# ice_header_adapter_pcb.net
KiCad netlist of a schematic drawn in EAGLE
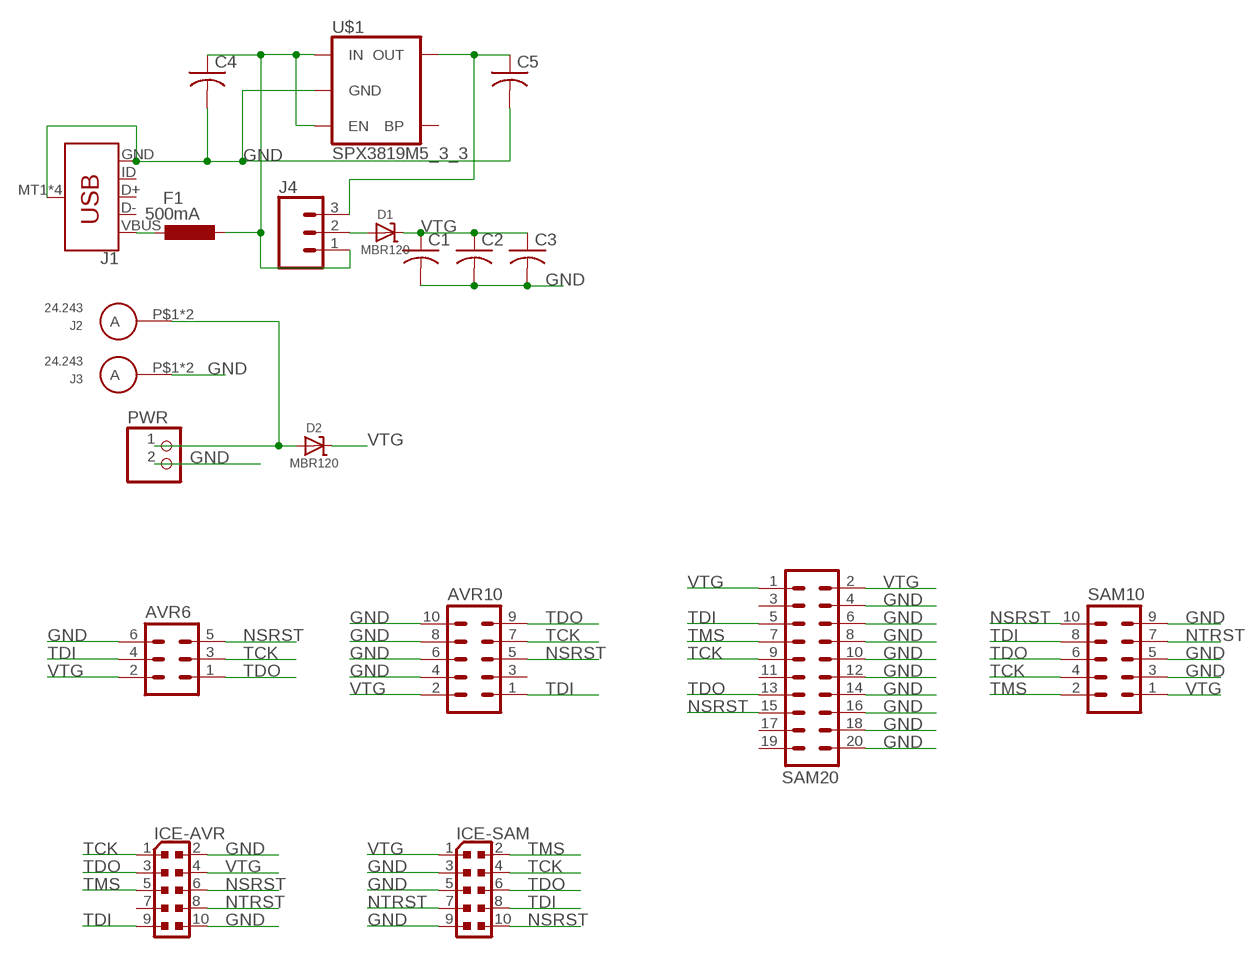
[diagram p0: schematic, sheet 1]

(export (version "E")
  (design (tool "Eeschema 10.0.6"))
  (components
    (comp (ref "AVR6")
      (value "ML6")
      (footprint "eagle-import:ML6")
      (libsource (lib "eagle-import") (part "ML6"))
    )
    (comp (ref "AVR10")
      (value "ML10")
      (footprint "eagle-import:ML10")
      (libsource (lib "eagle-import") (part "ML10"))
    )
    (comp (ref "C1")
      (value "C-USC0603")
      (footprint "eagle-import:C0603")
      (libsource (lib "eagle-import") (part "C-USC0603"))
    )
    (comp (ref "C2")
      (value "C-USC0603")
      (footprint "eagle-import:C0603")
      (libsource (lib "eagle-import") (part "C-USC0603"))
    )
    (comp (ref "C3")
      (value "C-USC0603")
      (footprint "eagle-import:C0603")
      (libsource (lib "eagle-import") (part "C-USC0603"))
    )
    (comp (ref "C4")
      (value "C-USC0603")
      (footprint "eagle-import:C0603")
      (libsource (lib "eagle-import") (part "C-USC0603"))
    )
    (comp (ref "C5")
      (value "C-USC0603")
      (footprint "eagle-import:C0603")
      (libsource (lib "eagle-import") (part "C-USC0603"))
    )
    (comp (ref "D1")
      (value "MBR120")
      (footprint "eagle-import:SOD-123")
      (libsource (lib "eagle-import") (part "DIODE-SCHOTTKYSOD-123"))
    )
    (comp (ref "D2")
      (value "MBR120")
      (footprint "eagle-import:SOD-123")
      (libsource (lib "eagle-import") (part "DIODE-SCHOTTKYSOD-123"))
    )
    (comp (ref "F1")
      (value "500mA")
      (footprint "eagle-import:L1812")
      (libsource (lib "eagle-import") (part "L-EUL1812"))
    )
    (comp (ref "ICE-AVR")
      (value "PINHEAD_PINHD-2X5PASSO127")
      (footprint "eagle-import:PINHEAD_2X05_127")
      (libsource (lib "eagle-import") (part "PINHEAD_PINHD-2X5PASSO127"))
    )
    (comp (ref "ICE-SAM")
      (value "PINHEAD_PINHD-2X5PASSO127")
      (footprint "eagle-import:PINHEAD_2X05_127")
      (libsource (lib "eagle-import") (part "PINHEAD_PINHD-2X5PASSO127"))
    )
    (comp (ref "J1")
      (value "USB_MICRO-B_SMT")
      (footprint "eagle-import:USB-MICROB")
      (libsource (lib "eagle-import") (part "USB_MICRO-B_SMT"))
    )
    (comp (ref "J2")
      (value "24.243")
      (footprint "eagle-import:24.243")
      (libsource (lib "eagle-import") (part "24.243"))
    )
    (comp (ref "J3")
      (value "24.243")
      (footprint "eagle-import:24.243")
      (libsource (lib "eagle-import") (part "24.243"))
    )
    (comp (ref "J4")
      (value "CONN_03LOCK")
      (footprint "eagle-import:1X03_LOCK")
      (libsource (lib "eagle-import") (part "CONN_03LOCK"))
    )
    (comp (ref "PWR")
      (value "PINHD-1X2/90")
      (footprint "eagle-import:1X02_90")
      (libsource (lib "eagle-import") (part "PINHD-1X2/90"))
    )
    (comp (ref "SAM10")
      (value "ML10")
      (footprint "eagle-import:ML10")
      (libsource (lib "eagle-import") (part "ML10"))
    )
    (comp (ref "SAM20")
      (value "ML20")
      (footprint "eagle-import:ML20")
      (libsource (lib "eagle-import") (part "ML20"))
    )
    (comp (ref "U$1")
      (value "SPX3819M5_3_3")
      (footprint "eagle-import:SOT23-5")
      (libsource (lib "eagle-import") (part "V_REG_SPX3819-SOT23-5"))
    )
  )
  (nets
    (net (code "1") (name "/GND") (class "Default")
      (node (ref "AVR10") (pin "10") (pinfunction "10_10") (pintype "passive"))
      (node (ref "AVR10") (pin "4") (pinfunction "4_4") (pintype "passive"))
      (node (ref "AVR10") (pin "6") (pinfunction "6_6") (pintype "passive"))
      (node (ref "AVR10") (pin "8") (pinfunction "8_8") (pintype "passive"))
      (node (ref "AVR6") (pin "6") (pinfunction "6_6") (pintype "passive"))
      (node (ref "C1") (pin "2") (pinfunction "2_2") (pintype "passive"))
      (node (ref "C2") (pin "2") (pinfunction "2_2") (pintype "passive"))
      (node (ref "C3") (pin "2") (pinfunction "2_2") (pintype "passive"))
      (node (ref "C4") (pin "2") (pinfunction "2_2") (pintype "passive"))
      (node (ref "C5") (pin "2") (pinfunction "2_2") (pintype "passive"))
      (node (ref "ICE-AVR") (pin "10") (pinfunction "10_10") (pintype "passive"))
      (node (ref "ICE-AVR") (pin "2") (pinfunction "2_2") (pintype "passive"))
      (node (ref "ICE-SAM") (pin "3") (pinfunction "3_3") (pintype "passive"))
      (node (ref "ICE-SAM") (pin "5") (pinfunction "5_5") (pintype "passive"))
      (node (ref "ICE-SAM") (pin "9") (pinfunction "9_9") (pintype "passive"))
      (node (ref "J1") (pin "GND") (pinfunction "GND_GND") (pintype "power_in"))
      (node (ref "J1") (pin "MT1") (pinfunction "SHIELD_MT1") (pintype "bidirectional"))
      (node (ref "J1") (pin "MT2") (pinfunction "SHIELD_MT2") (pintype "bidirectional"))
      (node (ref "J1") (pin "P$1") (pinfunction "SHIELD_P$1") (pintype "bidirectional"))
      (node (ref "J1") (pin "P$2") (pinfunction "SHIELD_P$2") (pintype "bidirectional"))
      (node (ref "J3") (pin "P$1") (pinfunction "A_P$1") (pintype "bidirectional"))
      (node (ref "J3") (pin "P$2") (pinfunction "A_P$2") (pintype "bidirectional"))
      (node (ref "PWR") (pin "2") (pinfunction "2_2") (pintype "passive"))
      (node (ref "SAM10") (pin "3") (pinfunction "3_3") (pintype "passive"))
      (node (ref "SAM10") (pin "5") (pinfunction "5_5") (pintype "passive"))
      (node (ref "SAM10") (pin "9") (pinfunction "9_9") (pintype "passive"))
      (node (ref "SAM20") (pin "10") (pinfunction "10_10") (pintype "passive"))
      (node (ref "SAM20") (pin "12") (pinfunction "12_12") (pintype "passive"))
      (node (ref "SAM20") (pin "14") (pinfunction "14_14") (pintype "passive"))
      (node (ref "SAM20") (pin "16") (pinfunction "16_16") (pintype "passive"))
      (node (ref "SAM20") (pin "18") (pinfunction "18_18") (pintype "passive"))
      (node (ref "SAM20") (pin "20") (pinfunction "20_20") (pintype "passive"))
      (node (ref "SAM20") (pin "4") (pinfunction "4_4") (pintype "passive"))
      (node (ref "SAM20") (pin "6") (pinfunction "6_6") (pintype "passive"))
      (node (ref "SAM20") (pin "8") (pinfunction "8_8") (pintype "passive"))
      (node (ref "U$1") (pin "2") (pinfunction "GND_2") (pintype "input"))
    )
    (net (code "2") (name "/NSRST") (class "Default")
      (node (ref "AVR10") (pin "5") (pinfunction "5_5") (pintype "passive"))
      (node (ref "AVR6") (pin "5") (pinfunction "5_5") (pintype "passive"))
      (node (ref "ICE-AVR") (pin "6") (pinfunction "6_6") (pintype "passive"))
      (node (ref "ICE-SAM") (pin "10") (pinfunction "10_10") (pintype "passive"))
      (node (ref "SAM10") (pin "10") (pinfunction "10_10") (pintype "passive"))
      (node (ref "SAM20") (pin "15") (pinfunction "15_15") (pintype "passive"))
    )
    (net (code "3") (name "/NTRST") (class "Default")
      (node (ref "ICE-AVR") (pin "8") (pinfunction "8_8") (pintype "passive"))
      (node (ref "ICE-SAM") (pin "7") (pinfunction "7_7") (pintype "passive"))
      (node (ref "SAM10") (pin "7") (pinfunction "7_7") (pintype "passive"))
    )
    (net (code "4") (name "/TCK") (class "Default")
      (node (ref "AVR10") (pin "7") (pinfunction "7_7") (pintype "passive"))
      (node (ref "AVR6") (pin "3") (pinfunction "3_3") (pintype "passive"))
      (node (ref "ICE-AVR") (pin "1") (pinfunction "1_1") (pintype "passive"))
      (node (ref "ICE-SAM") (pin "4") (pinfunction "4_4") (pintype "passive"))
      (node (ref "SAM10") (pin "4") (pinfunction "4_4") (pintype "passive"))
      (node (ref "SAM20") (pin "9") (pinfunction "9_9") (pintype "passive"))
    )
    (net (code "5") (name "/TDI") (class "Default")
      (node (ref "AVR10") (pin "1") (pinfunction "1_1") (pintype "passive"))
      (node (ref "AVR6") (pin "4") (pinfunction "4_4") (pintype "passive"))
      (node (ref "ICE-AVR") (pin "9") (pinfunction "9_9") (pintype "passive"))
      (node (ref "ICE-SAM") (pin "8") (pinfunction "8_8") (pintype "passive"))
      (node (ref "SAM10") (pin "8") (pinfunction "8_8") (pintype "passive"))
      (node (ref "SAM20") (pin "5") (pinfunction "5_5") (pintype "passive"))
    )
    (net (code "6") (name "/TDO") (class "Default")
      (node (ref "AVR10") (pin "9") (pinfunction "9_9") (pintype "passive"))
      (node (ref "AVR6") (pin "1") (pinfunction "1_1") (pintype "passive"))
      (node (ref "ICE-AVR") (pin "3") (pinfunction "3_3") (pintype "passive"))
      (node (ref "ICE-SAM") (pin "6") (pinfunction "6_6") (pintype "passive"))
      (node (ref "SAM10") (pin "6") (pinfunction "6_6") (pintype "passive"))
      (node (ref "SAM20") (pin "13") (pinfunction "13_13") (pintype "passive"))
    )
    (net (code "7") (name "/TMS") (class "Default")
      (node (ref "ICE-AVR") (pin "5") (pinfunction "5_5") (pintype "passive"))
      (node (ref "ICE-SAM") (pin "2") (pinfunction "2_2") (pintype "passive"))
      (node (ref "SAM10") (pin "2") (pinfunction "2_2") (pintype "passive"))
      (node (ref "SAM20") (pin "7") (pinfunction "7_7") (pintype "passive"))
    )
    (net (code "8") (name "/VTG") (class "Default")
      (node (ref "AVR10") (pin "2") (pinfunction "2_2") (pintype "passive"))
      (node (ref "AVR6") (pin "2") (pinfunction "2_2") (pintype "passive"))
      (node (ref "C1") (pin "1") (pinfunction "1_1") (pintype "passive"))
      (node (ref "C2") (pin "1") (pinfunction "1_1") (pintype "passive"))
      (node (ref "C3") (pin "1") (pinfunction "1_1") (pintype "passive"))
      (node (ref "D1") (pin "C") (pinfunction "C_C") (pintype "passive"))
      (node (ref "D2") (pin "C") (pinfunction "C_C") (pintype "passive"))
      (node (ref "ICE-AVR") (pin "4") (pinfunction "4_4") (pintype "passive"))
      (node (ref "ICE-SAM") (pin "1") (pinfunction "1_1") (pintype "passive"))
      (node (ref "SAM10") (pin "1") (pinfunction "1_1") (pintype "passive"))
      (node (ref "SAM20") (pin "1") (pinfunction "1_1") (pintype "passive"))
      (node (ref "SAM20") (pin "2") (pinfunction "2_2") (pintype "passive"))
    )
    (net (code "9") (name "Net-(D1-PadA)") (class "Default")
      (node (ref "D1") (pin "A") (pinfunction "A_A") (pintype "passive"))
      (node (ref "J4") (pin "2") (pinfunction "2_2") (pintype "passive"))
    )
    (net (code "10") (name "Net-(D2-PadA)") (class "Default")
      (node (ref "D2") (pin "A") (pinfunction "A_A") (pintype "passive"))
      (node (ref "J2") (pin "P$1") (pinfunction "A_P$1") (pintype "bidirectional"))
      (node (ref "J2") (pin "P$2") (pinfunction "A_P$2") (pintype "bidirectional"))
      (node (ref "PWR") (pin "1") (pinfunction "1_1") (pintype "passive"))
    )
    (net (code "11") (name "Net-(F1-Pad2)") (class "Default")
      (node (ref "F1") (pin "2") (pinfunction "2_2") (pintype "passive"))
      (node (ref "J1") (pin "VBUS") (pinfunction "VBUS_VBUS") (pintype "power_in"))
    )
    (net (code "12") (name "Net-(U$1-EN)") (class "Default")
      (node (ref "C4") (pin "1") (pinfunction "1_1") (pintype "passive"))
      (node (ref "F1") (pin "1") (pinfunction "1_1") (pintype "passive"))
      (node (ref "J4") (pin "1") (pinfunction "1_1") (pintype "passive"))
      (node (ref "U$1") (pin "1") (pinfunction "IN_1") (pintype "input"))
      (node (ref "U$1") (pin "3") (pinfunction "EN_3") (pintype "input"))
    )
    (net (code "13") (name "Net-(U$1-OUT)") (class "Default")
      (node (ref "C5") (pin "1") (pinfunction "1_1") (pintype "passive"))
      (node (ref "J4") (pin "3") (pinfunction "3_3") (pintype "passive"))
      (node (ref "U$1") (pin "5") (pinfunction "OUT_5") (pintype "passive"))
    )
    (net (code "14") (name "unconnected-(AVR10-Pad3)") (class "Default")
      (node (ref "AVR10") (pin "3") (pinfunction "3_3") (pintype "passive"))
    )
    (net (code "15") (name "unconnected-(ICE-AVR-Pad7)") (class "Default")
      (node (ref "ICE-AVR") (pin "7") (pinfunction "7_7") (pintype "passive"))
    )
    (net (code "16") (name "unconnected-(J1-PadD+)") (class "Default")
      (node (ref "J1") (pin "D+") (pinfunction "D+_D+") (pintype "bidirectional"))
    )
    (net (code "17") (name "unconnected-(J1-PadD-)") (class "Default")
      (node (ref "J1") (pin "D-") (pinfunction "D-_D-") (pintype "bidirectional"))
    )
    (net (code "18") (name "unconnected-(J1-PadID)") (class "Default")
      (node (ref "J1") (pin "ID") (pinfunction "ID_ID") (pintype "bidirectional"))
    )
    (net (code "19") (name "unconnected-(SAM20-Pad3)") (class "Default")
      (node (ref "SAM20") (pin "3") (pinfunction "3_3") (pintype "passive"))
    )
    (net (code "20") (name "unconnected-(SAM20-Pad11)") (class "Default")
      (node (ref "SAM20") (pin "11") (pinfunction "11_11") (pintype "passive"))
    )
    (net (code "21") (name "unconnected-(SAM20-Pad17)") (class "Default")
      (node (ref "SAM20") (pin "17") (pinfunction "17_17") (pintype "passive"))
    )
    (net (code "22") (name "unconnected-(SAM20-Pad19)") (class "Default")
      (node (ref "SAM20") (pin "19") (pinfunction "19_19") (pintype "passive"))
    )
    (net (code "23") (name "unconnected-(U$1-BP-Pad4)") (class "Default")
      (node (ref "U$1") (pin "4") (pinfunction "BP_4") (pintype "input"))
    )
  )
)
